# YCCC_Stack.net
KiCad netlist of a schematic drawn in EAGLE
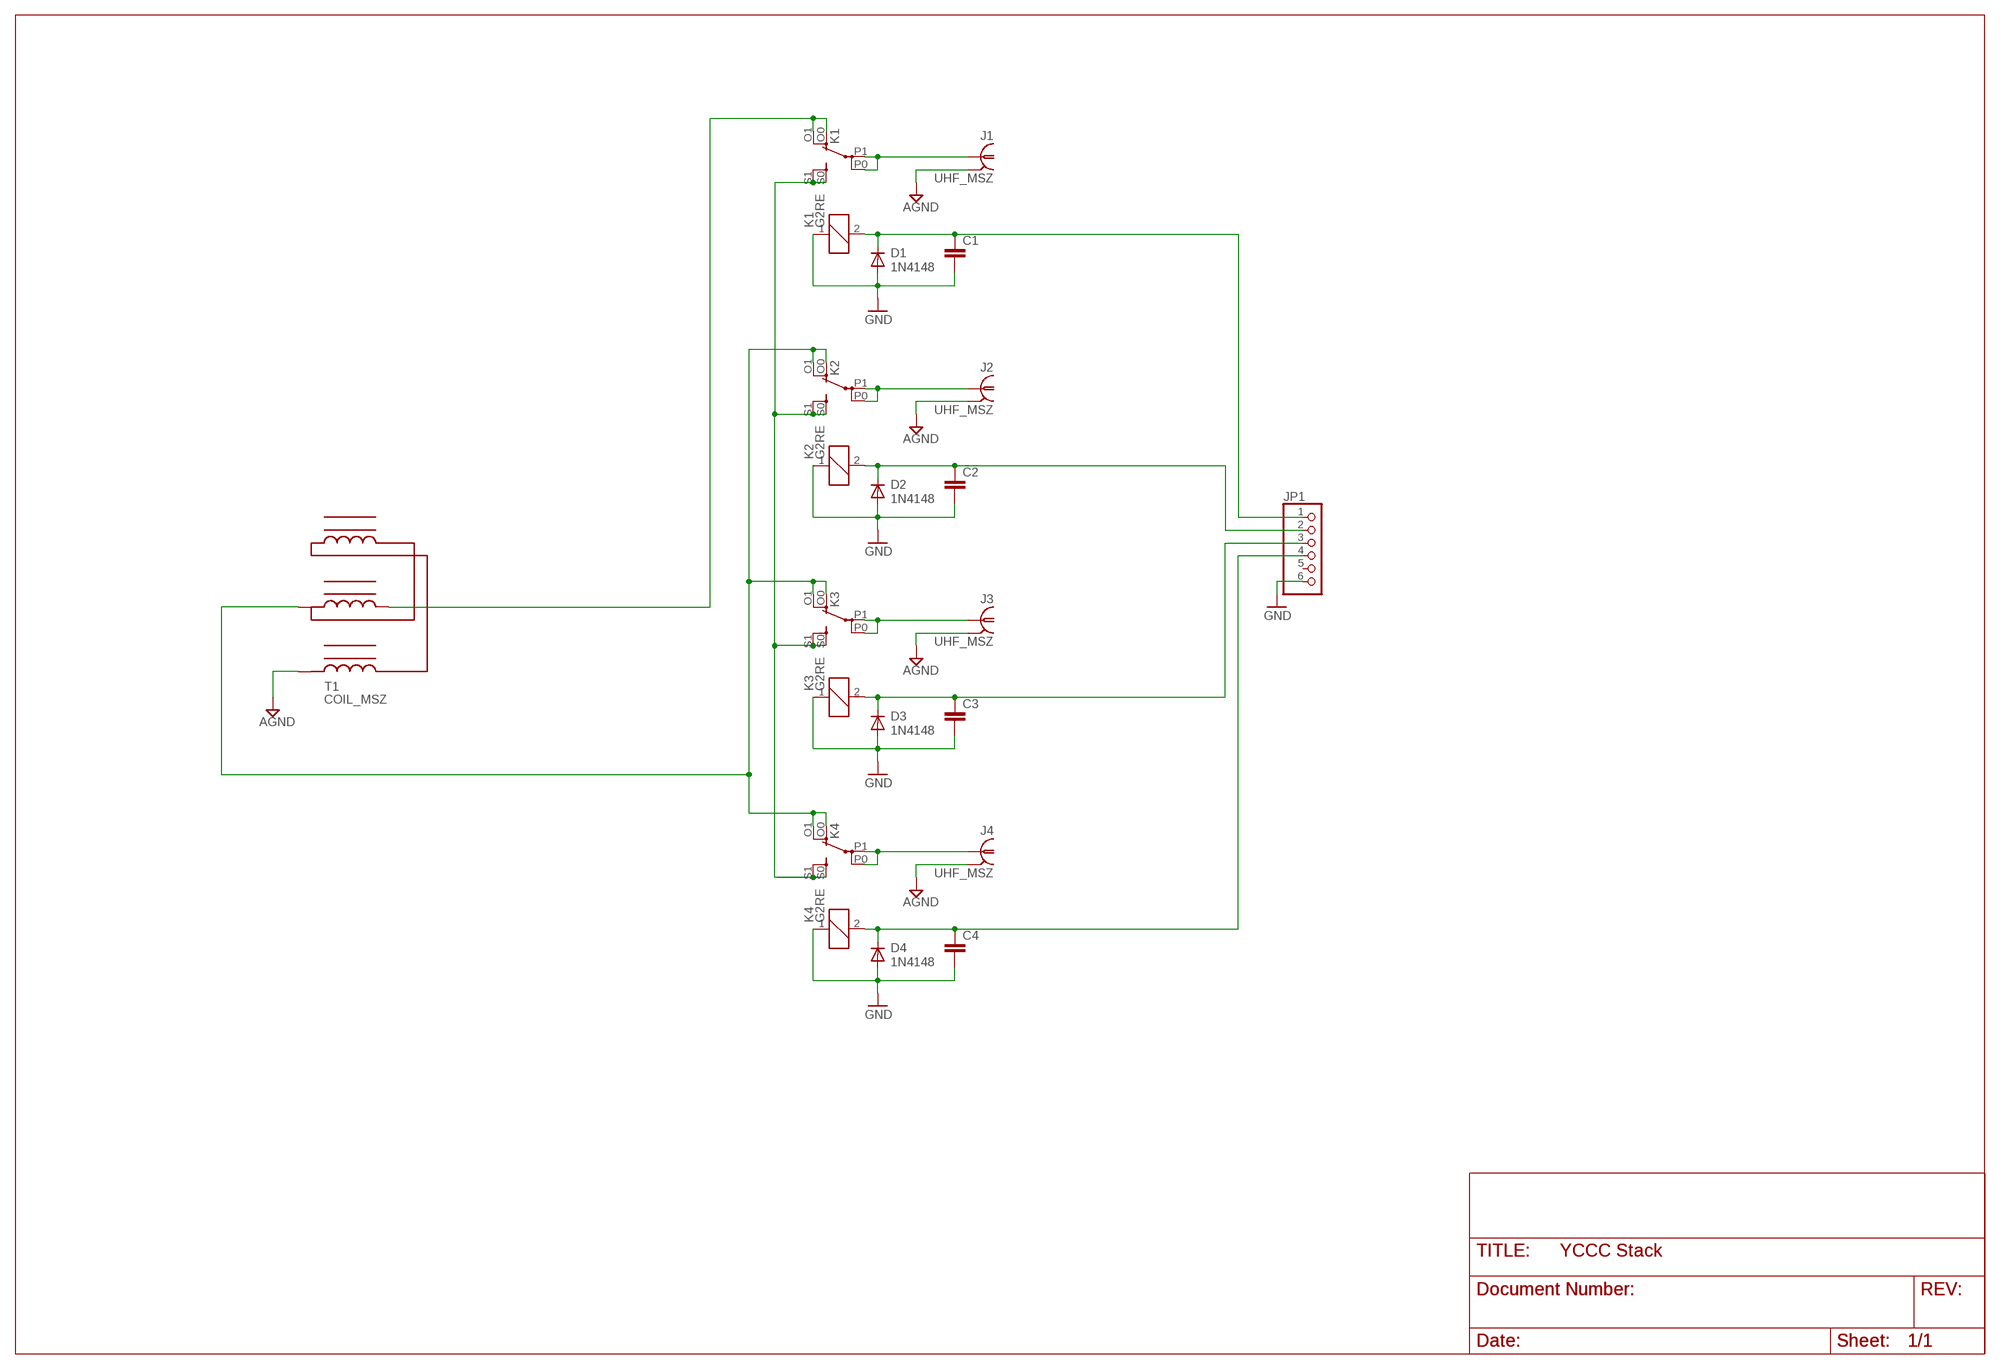
[diagram p0: schematic, sheet 1]

(export (version "E")
  (design (tool "Eeschema 10.0.6"))
  (components
    (comp (ref "C1")
      (value "C-EU050-035X075")
      (footprint "eagle-import:C050-035X075")
      (libsource (lib "eagle-import") (part "C-EU050-035X075"))
    )
    (comp (ref "C2")
      (value "C-EU050-035X075")
      (footprint "eagle-import:C050-035X075")
      (libsource (lib "eagle-import") (part "C-EU050-035X075"))
    )
    (comp (ref "C3")
      (value "C-EU050-035X075")
      (footprint "eagle-import:C050-035X075")
      (libsource (lib "eagle-import") (part "C-EU050-035X075"))
    )
    (comp (ref "C4")
      (value "C-EU050-035X075")
      (footprint "eagle-import:C050-035X075")
      (libsource (lib "eagle-import") (part "C-EU050-035X075"))
    )
    (comp (ref "D1")
      (value "1N4148")
      (footprint "eagle-import:DO35-7")
      (libsource (lib "eagle-import") (part "1N4148DO35-7"))
    )
    (comp (ref "D2")
      (value "1N4148")
      (footprint "eagle-import:DO35-7")
      (libsource (lib "eagle-import") (part "1N4148DO35-7"))
    )
    (comp (ref "D3")
      (value "1N4148")
      (footprint "eagle-import:DO35-7")
      (libsource (lib "eagle-import") (part "1N4148DO35-7"))
    )
    (comp (ref "D4")
      (value "1N4148")
      (footprint "eagle-import:DO35-7")
      (libsource (lib "eagle-import") (part "1N4148DO35-7"))
    )
    (comp (ref "J1")
      (value "UHF_MSZ")
      (footprint "eagle-import:BNC_MSZ")
      (libsource (lib "eagle-import") (part "UHF_MSZ"))
    )
    (comp (ref "J2")
      (value "UHF_MSZ")
      (footprint "eagle-import:BNC_MSZ")
      (libsource (lib "eagle-import") (part "UHF_MSZ"))
    )
    (comp (ref "J3")
      (value "UHF_MSZ")
      (footprint "eagle-import:BNC_MSZ")
      (libsource (lib "eagle-import") (part "UHF_MSZ"))
    )
    (comp (ref "J4")
      (value "UHF_MSZ")
      (footprint "eagle-import:BNC_MSZ")
      (libsource (lib "eagle-import") (part "UHF_MSZ"))
    )
    (comp (ref "JP1")
      (value "PINHD-1X6")
      (footprint "eagle-import:1X06")
      (libsource (lib "eagle-import") (part "PINHD-1X6"))
    )
    (comp (ref "K1")
      (value "G2RE")
      (footprint "eagle-import:G2RE")
      (libsource (lib "eagle-import") (part "G2RE"))
    )
    (comp (ref "K2")
      (value "G2RE")
      (footprint "eagle-import:G2RE")
      (libsource (lib "eagle-import") (part "G2RE"))
    )
    (comp (ref "K3")
      (value "G2RE")
      (footprint "eagle-import:G2RE")
      (libsource (lib "eagle-import") (part "G2RE"))
    )
    (comp (ref "K4")
      (value "G2RE")
      (footprint "eagle-import:G2RE")
      (libsource (lib "eagle-import") (part "G2RE"))
    )
    (comp (ref "T1")
      (value "COIL_MSZ")
      (footprint "eagle-import:COIL_MSZ")
      (libsource (lib "eagle-import") (part "COIL_MSZ"))
    )
  )
  (nets
    (net (code "1") (name "AGND") (class "Default")
      (node (ref "J1") (pin "P$1") (pinfunction "GND_P$1") (pintype "power_in"))
      (node (ref "J2") (pin "P$1") (pinfunction "GND_P$1") (pintype "power_in"))
      (node (ref "J3") (pin "P$1") (pinfunction "GND_P$1") (pintype "power_in"))
      (node (ref "J4") (pin "P$1") (pinfunction "GND_P$1") (pintype "power_in"))
      (node (ref "T1") (pin "3") (pinfunction "GND_3") (pintype "passive"))
    )
    (net (code "2") (name "GND") (class "Default")
      (node (ref "C1") (pin "2") (pinfunction "2_2") (pintype "passive"))
      (node (ref "C2") (pin "2") (pinfunction "2_2") (pintype "passive"))
      (node (ref "C3") (pin "2") (pinfunction "2_2") (pintype "passive"))
      (node (ref "C4") (pin "2") (pinfunction "2_2") (pintype "passive"))
      (node (ref "D1") (pin "A") (pinfunction "A_A") (pintype "passive"))
      (node (ref "D2") (pin "A") (pinfunction "A_A") (pintype "passive"))
      (node (ref "D3") (pin "A") (pinfunction "A_A") (pintype "passive"))
      (node (ref "D4") (pin "A") (pinfunction "A_A") (pintype "passive"))
      (node (ref "JP1") (pin "6") (pinfunction "6_6") (pintype "passive"))
      (node (ref "K1") (pin "1") (pinfunction "1_1") (pintype "passive"))
      (node (ref "K2") (pin "1") (pinfunction "1_1") (pintype "passive"))
      (node (ref "K3") (pin "1") (pinfunction "1_1") (pintype "passive"))
      (node (ref "K4") (pin "1") (pinfunction "1_1") (pintype "passive"))
    )
    (net (code "3") (name "Net-(C1-Pad1)") (class "Default")
      (node (ref "C1") (pin "1") (pinfunction "1_1") (pintype "passive"))
      (node (ref "D1") (pin "C") (pinfunction "C_C") (pintype "passive"))
      (node (ref "JP1") (pin "1") (pinfunction "1_1") (pintype "passive"))
      (node (ref "K1") (pin "2") (pinfunction "2_2") (pintype "passive"))
    )
    (net (code "4") (name "Net-(C2-Pad1)") (class "Default")
      (node (ref "C2") (pin "1") (pinfunction "1_1") (pintype "passive"))
      (node (ref "D2") (pin "C") (pinfunction "C_C") (pintype "passive"))
      (node (ref "JP1") (pin "2") (pinfunction "2_2") (pintype "passive"))
      (node (ref "K2") (pin "2") (pinfunction "2_2") (pintype "passive"))
    )
    (net (code "5") (name "Net-(C3-Pad1)") (class "Default")
      (node (ref "C3") (pin "1") (pinfunction "1_1") (pintype "passive"))
      (node (ref "D3") (pin "C") (pinfunction "C_C") (pintype "passive"))
      (node (ref "JP1") (pin "3") (pinfunction "3_3") (pintype "passive"))
      (node (ref "K3") (pin "2") (pinfunction "2_2") (pintype "passive"))
    )
    (net (code "6") (name "Net-(C4-Pad1)") (class "Default")
      (node (ref "C4") (pin "1") (pinfunction "1_1") (pintype "passive"))
      (node (ref "D4") (pin "C") (pinfunction "C_C") (pintype "passive"))
      (node (ref "JP1") (pin "4") (pinfunction "4_4") (pintype "passive"))
      (node (ref "K4") (pin "2") (pinfunction "2_2") (pintype "passive"))
    )
    (net (code "7") (name "Net-(J1-1)") (class "Default")
      (node (ref "J1") (pin "P$2") (pinfunction "1_P$2") (pintype "passive"))
      (node (ref "K1") (pin "P0") (pinfunction "P_P0") (pintype "passive"))
      (node (ref "K1") (pin "P1") (pinfunction "P_P1") (pintype "passive"))
    )
    (net (code "8") (name "Net-(J2-1)") (class "Default")
      (node (ref "J2") (pin "P$2") (pinfunction "1_P$2") (pintype "passive"))
      (node (ref "K2") (pin "P0") (pinfunction "P_P0") (pintype "passive"))
      (node (ref "K2") (pin "P1") (pinfunction "P_P1") (pintype "passive"))
    )
    (net (code "9") (name "Net-(J3-1)") (class "Default")
      (node (ref "J3") (pin "P$2") (pinfunction "1_P$2") (pintype "passive"))
      (node (ref "K3") (pin "P0") (pinfunction "P_P0") (pintype "passive"))
      (node (ref "K3") (pin "P1") (pinfunction "P_P1") (pintype "passive"))
    )
    (net (code "10") (name "Net-(J4-1)") (class "Default")
      (node (ref "J4") (pin "P$2") (pinfunction "1_P$2") (pintype "passive"))
      (node (ref "K4") (pin "P0") (pinfunction "P_P0") (pintype "passive"))
      (node (ref "K4") (pin "P1") (pinfunction "P_P1") (pintype "passive"))
    )
    (net (code "11") (name "Net-(K1B-S-PadS0)") (class "Default")
      (node (ref "K1") (pin "S0") (pinfunction "S_S0") (pintype "passive"))
      (node (ref "K1") (pin "S1") (pinfunction "S_S1") (pintype "passive"))
      (node (ref "K2") (pin "S0") (pinfunction "S_S0") (pintype "passive"))
      (node (ref "K2") (pin "S1") (pinfunction "S_S1") (pintype "passive"))
      (node (ref "K3") (pin "S0") (pinfunction "S_S0") (pintype "passive"))
      (node (ref "K3") (pin "S1") (pinfunction "S_S1") (pintype "passive"))
      (node (ref "K4") (pin "S0") (pinfunction "S_S0") (pintype "passive"))
      (node (ref "K4") (pin "S1") (pinfunction "S_S1") (pintype "passive"))
    )
    (net (code "12") (name "Net-(T1-22)") (class "Default")
      (node (ref "K2") (pin "O0") (pinfunction "O_O0") (pintype "passive"))
      (node (ref "K2") (pin "O1") (pinfunction "O_O1") (pintype "passive"))
      (node (ref "K3") (pin "O0") (pinfunction "O_O0") (pintype "passive"))
      (node (ref "K3") (pin "O1") (pinfunction "O_O1") (pintype "passive"))
      (node (ref "K4") (pin "O0") (pinfunction "O_O0") (pintype "passive"))
      (node (ref "K4") (pin "O1") (pinfunction "O_O1") (pintype "passive"))
      (node (ref "T1") (pin "2") (pinfunction "22_2") (pintype "passive"))
    )
    (net (code "13") (name "Net-(T1-50)") (class "Default")
      (node (ref "K1") (pin "O0") (pinfunction "O_O0") (pintype "passive"))
      (node (ref "K1") (pin "O1") (pinfunction "O_O1") (pintype "passive"))
      (node (ref "T1") (pin "1") (pinfunction "50_1") (pintype "passive"))
    )
    (net (code "14") (name "unconnected-(JP1-Pad5)") (class "Default")
      (node (ref "JP1") (pin "5") (pinfunction "5_5") (pintype "passive"))
    )
  )
)
